# ProPrj_esp32_pressure_sensor_2026-01-10.net
KiCad netlist of a schematic drawn in EasyEDA Pro
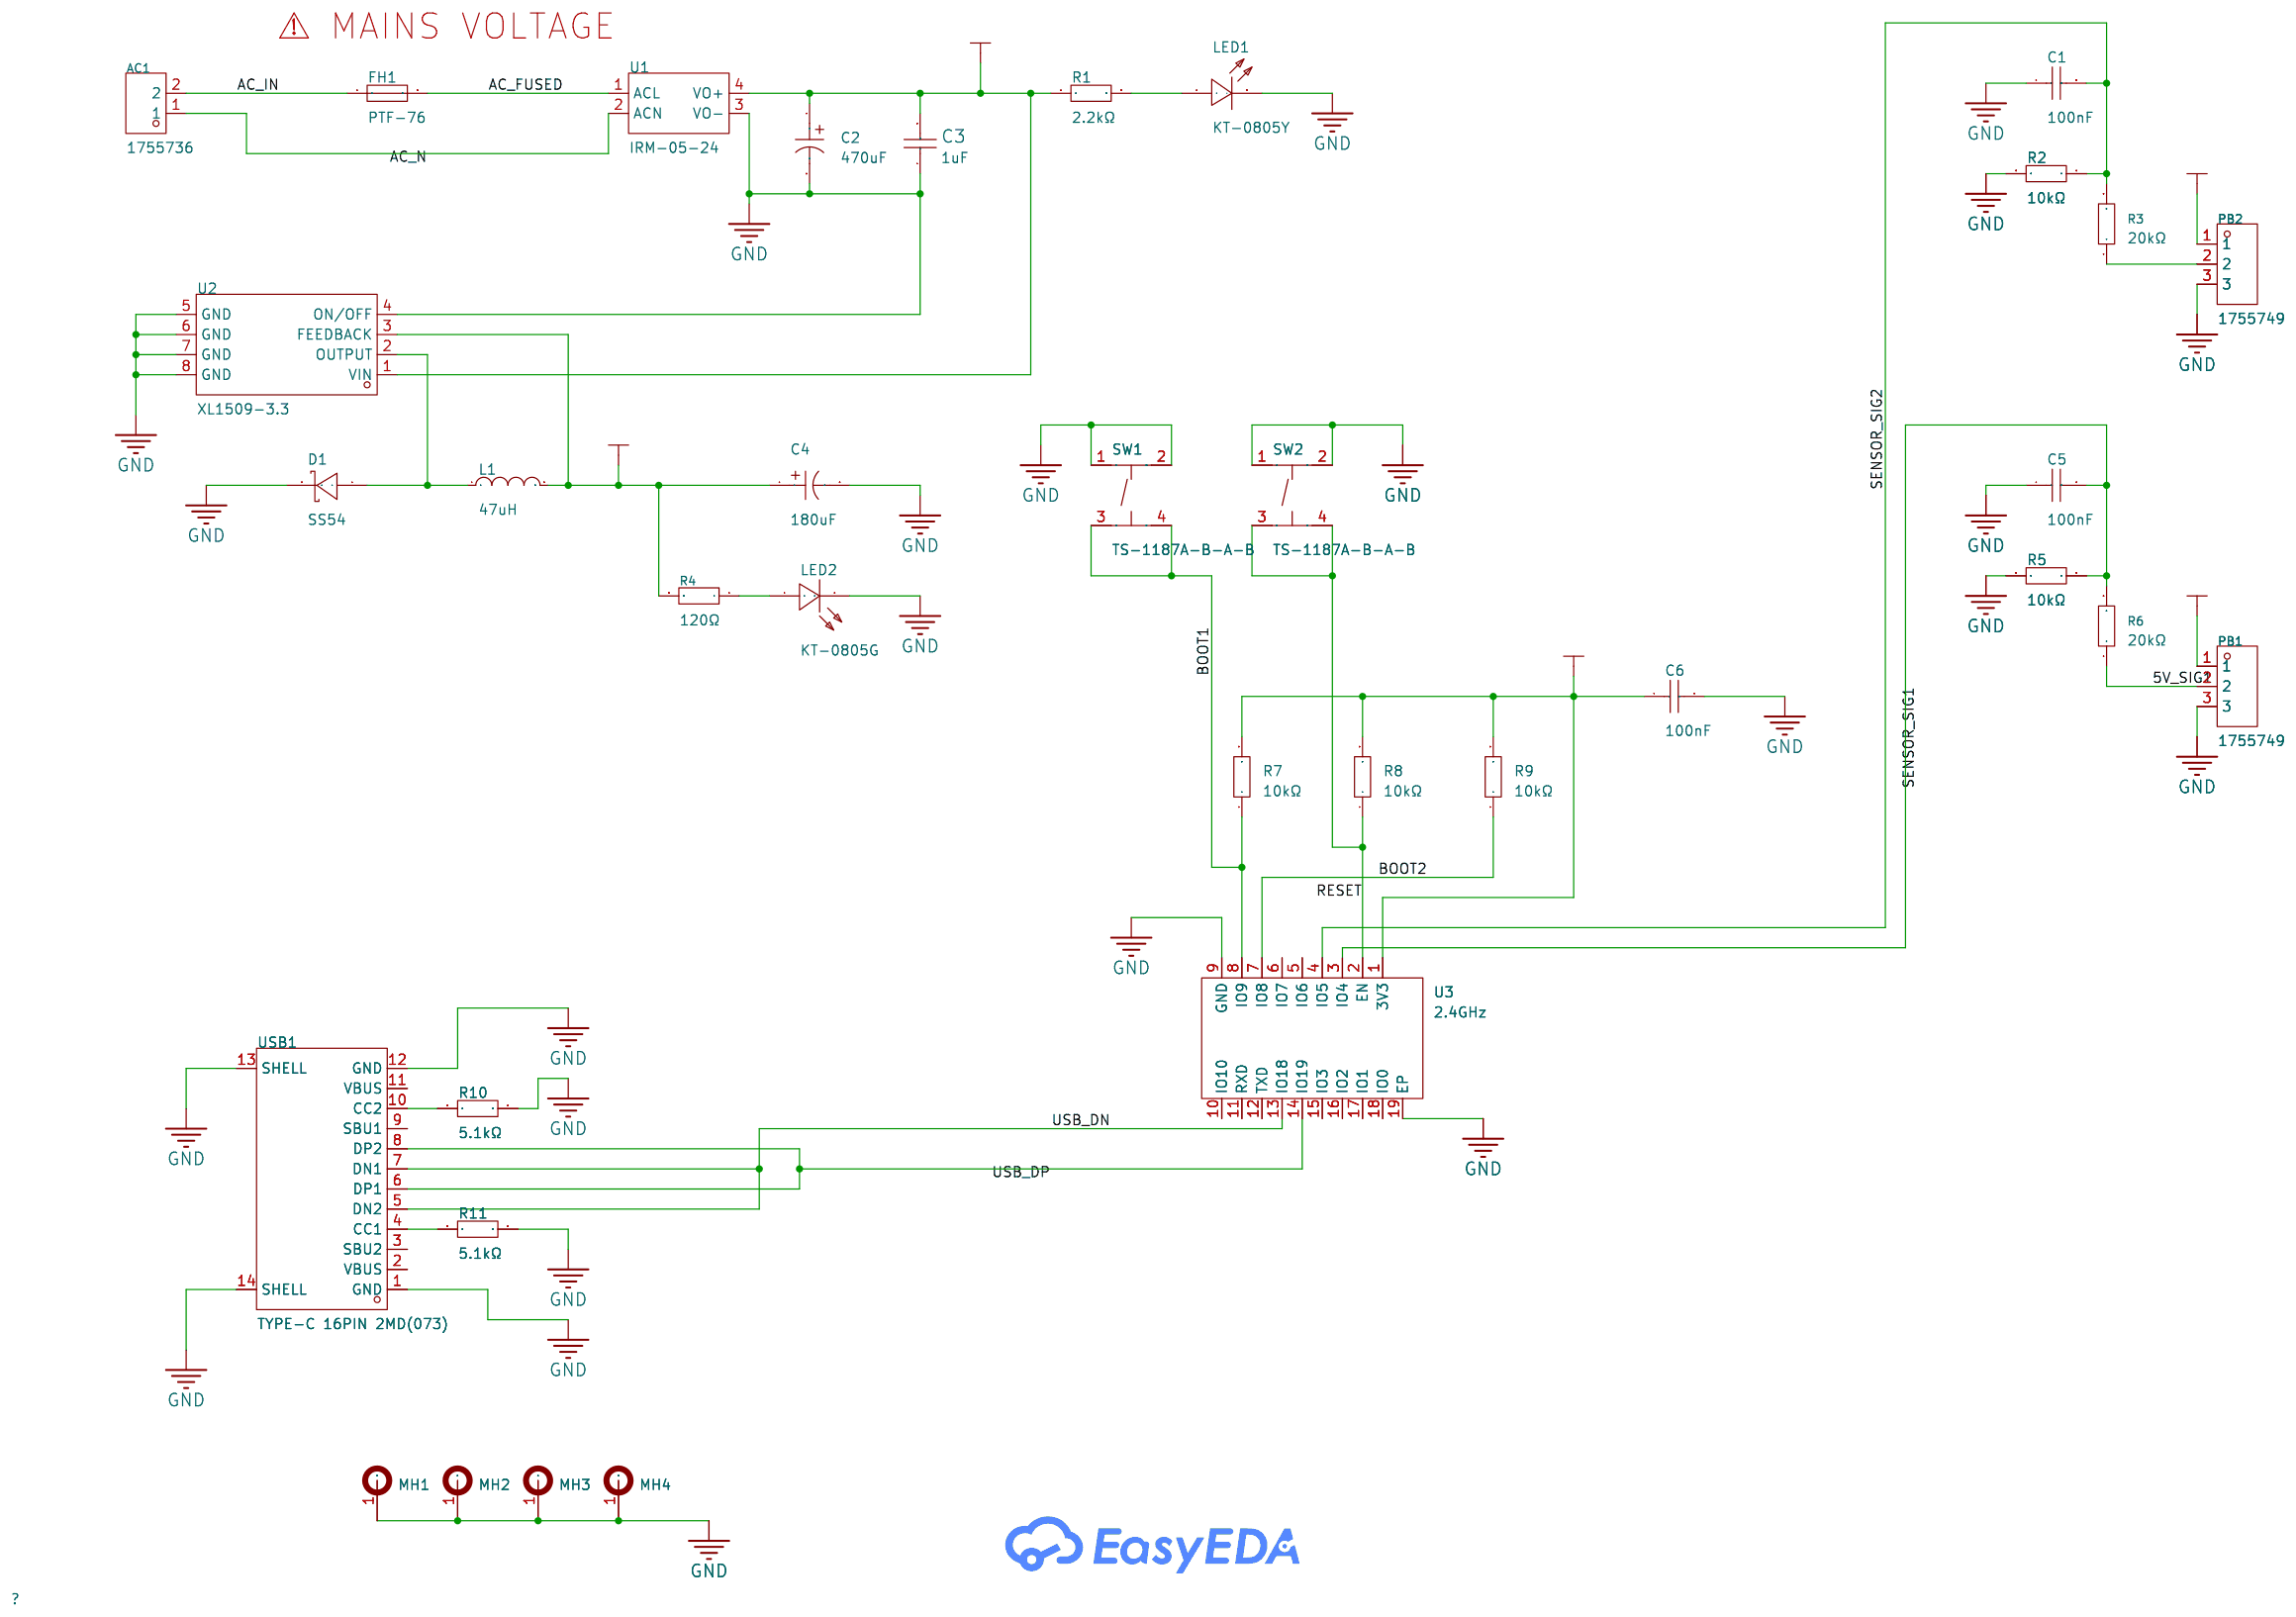
[diagram p0: schematic sheet]

(export (version "E")
  (design (tool "Eeschema 10.0.6"))
  (components
    (comp (ref "AC1")
      (value "1755736")
      (footprint "easyedapro:CONN-TH_1755736")
      (fields (field (name "Manufacturer") "Phoenix Contact(菲尼克斯)"))
      (libsource (lib "easyedapro") (part "1755736"))
    )
    (comp (ref "C1")
      (value "100nF")
      (footprint "easyedapro:C0805")
      (description "Capacitance:100nF Tolerance:±10% Tolerance:±10% Voltage Rating:100V Temperature Coefficient:X7R")
      (fields
        (field (name "Manufacturer Part") "CL21B104KCFNNNE")
        (field (name "Manufacturer") "SAMSUNG(三星)")
      )
      (libsource (lib "easyedapro") (part "CL21B104KCFNNNE"))
    )
    (comp (ref "C2")
      (value "470uF")
      (footprint "easyedapro:CAP-SMD_BD10.0-L10.3-W10.3-LS11.0-FD")
      (fields (field (name "Manufacturer Part") "JVE25V470M10X10") (field (name "Manufacturer") "JIERR(捷而瑞)"))
      (libsource (lib "easyedapro") (part "JVE25V470M10X10"))
    )
    (comp (ref "C3")
      (value "1uF")
      (footprint "easyedapro:C0805")
      (description "Capacitance:1uF Tolerance:±10% Tolerance:±10% Voltage Rating:50V Temperature Coefficient:X7R")
      (fields
        (field (name "Manufacturer Part") "CL21B105KBFNNNE")
        (field (name "Manufacturer") "SAMSUNG(三星)")
      )
      (libsource (lib "easyedapro") (part "CL21B105KBFNNNE"))
    )
    (comp (ref "C4")
      (value "180uF")
      (footprint "easyedapro:CAP-SMD_BD6.3-L6.6-W6.6-LS7.4-FD")
      (fields (field (name "Manufacturer Part") "RVT25V180M6X8") (field (name "Manufacturer") "JIERR(捷而瑞)"))
      (libsource (lib "easyedapro") (part "RVT25V180M6X8"))
    )
    (comp (ref "C5")
      (value "100nF")
      (footprint "easyedapro:C0805")
      (description "Capacitance:100nF Tolerance:±10% Tolerance:±10% Voltage Rating:100V Temperature Coefficient:X7R")
      (fields
        (field (name "Manufacturer Part") "CL21B104KCFNNNE")
        (field (name "Manufacturer") "SAMSUNG(三星)")
      )
      (libsource (lib "easyedapro") (part "CL21B104KCFNNNE"))
    )
    (comp (ref "C6")
      (value "100nF")
      (footprint "easyedapro:C0805")
      (description "Capacitance:100nF Tolerance:±10% Tolerance:±10% Voltage Rating:100V Temperature Coefficient:X7R")
      (fields
        (field (name "Manufacturer Part") "CL21B104KCFNNNE")
        (field (name "Manufacturer") "SAMSUNG(三星)")
      )
      (libsource (lib "easyedapro") (part "CL21B104KCFNNNE"))
    )
    (comp (ref "D1")
      (value "SS54")
      (footprint "easyedapro:SMA_L4.4-W2.8-LS5.4-R-RD")
      (fields (field (name "Manufacturer") "MDD(辰达半导体)"))
      (libsource (lib "easyedapro") (part "SS54_C22452"))
    )
    (comp (ref "FH1")
      (value "PTF-76")
      (footprint "easyedapro:FUSE-TH_L25.2-W9.8_PTF-76")
      (fields (field (name "Manufacturer") "XFCN(兴飞)"))
      (libsource (lib "easyedapro") (part "PTF-76"))
    )
    (comp (ref "L1")
      (value "47uH")
      (footprint "easyedapro:IND-SMD_L4.5-W4.0")
      (fields (field (name "Manufacturer Part") "CY43-47UH") (field (name "Manufacturer") "SHOU HAN(首韩)"))
      (libsource (lib "easyedapro") (part "CY43-47UH"))
    )
    (comp (ref "LED1")
      (value "KT-0805Y")
      (footprint "easyedapro:LED0805-R-RD")
      (fields (field (name "Manufacturer") "KENTO"))
      (libsource (lib "easyedapro") (part "17-21SUYC/TR8"))
    )
    (comp (ref "LED2")
      (value "KT-0805G")
      (footprint "easyedapro:LED0805-R-RD")
      (fields (field (name "Manufacturer") "KENTO"))
      (libsource (lib "easyedapro") (part "0805G (Green)"))
    )
    (comp (ref "MH1")
      (value "~")
      (footprint "easyedapro:MH_7.5x2.7mm")
      (libsource (lib "easyedapro") (part "MH_7.5x2.7mm"))
    )
    (comp (ref "MH2")
      (value "~")
      (footprint "easyedapro:MH_7.5x2.7mm")
      (libsource (lib "easyedapro") (part "MH_7.5x2.7mm"))
    )
    (comp (ref "MH3")
      (value "~")
      (footprint "easyedapro:MH_7.5x2.7mm")
      (libsource (lib "easyedapro") (part "MH_7.5x2.7mm"))
    )
    (comp (ref "MH4")
      (value "~")
      (footprint "easyedapro:MH_7.5x2.7mm")
      (libsource (lib "easyedapro") (part "MH_7.5x2.7mm"))
    )
    (comp (ref "PB1")
      (value "1755749")
      (footprint "easyedapro:CONN-TH_1755749")
      (fields (field (name "Manufacturer") "Phoenix Contact(菲尼克斯)"))
      (libsource (lib "easyedapro") (part "1755749"))
    )
    (comp (ref "PB2")
      (value "1755749")
      (footprint "easyedapro:CONN-TH_1755749")
      (fields (field (name "Manufacturer") "Phoenix Contact(菲尼克斯)"))
      (libsource (lib "easyedapro") (part "1755749"))
    )
    (comp (ref "R1")
      (value "2.2kΩ")
      (footprint "easyedapro:R0805")
      (fields
        (field (name "Manufacturer Part") "0805W8F2201T5E")
        (field (name "Manufacturer") "UNI-ROYAL(厚声)")
      )
      (libsource (lib "easyedapro") (part "0805W8F2201T5E"))
    )
    (comp (ref "R2")
      (value "10kΩ")
      (footprint "easyedapro:R0805")
      (fields
        (field (name "Manufacturer Part") "0805W8F1002T5E")
        (field (name "Manufacturer") "UNI-ROYAL(厚声)")
      )
      (libsource (lib "easyedapro") (part "0805W8F1002T5E"))
    )
    (comp (ref "R3")
      (value "20kΩ")
      (footprint "easyedapro:R0805")
      (fields
        (field (name "Manufacturer Part") "0805W8F2002T5E")
        (field (name "Manufacturer") "UNI-ROYAL(厚声)")
      )
      (libsource (lib "easyedapro") (part "0805W8F2002T5E"))
    )
    (comp (ref "R4")
      (value "120Ω")
      (footprint "easyedapro:R0805")
      (fields
        (field (name "Manufacturer Part") "0805W8F1200T5E")
        (field (name "Manufacturer") "UNI-ROYAL(厚声)")
      )
      (libsource (lib "easyedapro") (part "0805W8F1200T5E"))
    )
    (comp (ref "R5")
      (value "10kΩ")
      (footprint "easyedapro:R0805")
      (fields
        (field (name "Manufacturer Part") "0805W8F1002T5E")
        (field (name "Manufacturer") "UNI-ROYAL(厚声)")
      )
      (libsource (lib "easyedapro") (part "0805W8F1002T5E"))
    )
    (comp (ref "R6")
      (value "20kΩ")
      (footprint "easyedapro:R0805")
      (fields
        (field (name "Manufacturer Part") "0805W8F2002T5E")
        (field (name "Manufacturer") "UNI-ROYAL(厚声)")
      )
      (libsource (lib "easyedapro") (part "0805W8F2002T5E"))
    )
    (comp (ref "R7")
      (value "10kΩ")
      (footprint "easyedapro:R0805")
      (fields
        (field (name "Manufacturer Part") "0805W8F1002T5E")
        (field (name "Manufacturer") "UNI-ROYAL(厚声)")
      )
      (libsource (lib "easyedapro") (part "0805W8F1002T5E"))
    )
    (comp (ref "R8")
      (value "10kΩ")
      (footprint "easyedapro:R0805")
      (fields
        (field (name "Manufacturer Part") "0805W8F1002T5E")
        (field (name "Manufacturer") "UNI-ROYAL(厚声)")
      )
      (libsource (lib "easyedapro") (part "0805W8F1002T5E"))
    )
    (comp (ref "R9")
      (value "10kΩ")
      (footprint "easyedapro:R0805")
      (fields
        (field (name "Manufacturer Part") "0805W8F1002T5E")
        (field (name "Manufacturer") "UNI-ROYAL(厚声)")
      )
      (libsource (lib "easyedapro") (part "0805W8F1002T5E"))
    )
    (comp (ref "R10")
      (value "5.1kΩ")
      (footprint "easyedapro:R0805")
      (fields
        (field (name "Manufacturer Part") "0805W8F5101T5E")
        (field (name "Manufacturer") "UNI-ROYAL(厚声)")
      )
      (libsource (lib "easyedapro") (part "0805W8F5101T5E"))
    )
    (comp (ref "R11")
      (value "5.1kΩ")
      (footprint "easyedapro:R0805")
      (fields
        (field (name "Manufacturer Part") "0805W8F5101T5E")
        (field (name "Manufacturer") "UNI-ROYAL(厚声)")
      )
      (libsource (lib "easyedapro") (part "0805W8F5101T5E"))
    )
    (comp (ref "SW1")
      (value "TS-1187A-B-A-B")
      (footprint "easyedapro:SW-SMD_4P-L5.1-W5.1-P3.70-LS6.5-TL_H1.5")
      (fields (field (name "Manufacturer") "XKB Connection(中国星坤)"))
      (libsource (lib "easyedapro") (part "TS-1187A-B-A-B"))
    )
    (comp (ref "SW2")
      (value "TS-1187A-B-A-B")
      (footprint "easyedapro:SW-SMD_4P-L5.1-W5.1-P3.70-LS6.5-TL_H1.5")
      (fields (field (name "Manufacturer") "XKB Connection(中国星坤)"))
      (libsource (lib "easyedapro") (part "TS-1187A-B-A-B"))
    )
    (comp (ref "U1")
      (value "IRM-05-24")
      (footprint "easyedapro:PWRM-TH_IRM-05-XX")
      (fields (field (name "Manufacturer") "MW(明纬)"))
      (libsource (lib "easyedapro") (part "IRM-05-24"))
    )
    (comp (ref "U2")
      (value "XL1509-3.3")
      (footprint "easyedapro:SOIC-8_L4.9-W3.9-P1.27-LS6.0-BL")
      (fields (field (name "Manufacturer") "UMW(友台半导体)"))
      (libsource (lib "easyedapro") (part "XL1509-3.3"))
    )
    (comp (ref "U3")
      (value "2.4GHz")
      (footprint "easyedapro:BULETM-SMD_ESPRESSIF_ESP32-C3-WROOM-02-N4-4MB")
      (fields
        (field (name "Manufacturer Part") "ESP32-C3-WROOM-02-N4")
        (field (name "Manufacturer") "ESPRESSIF(乐鑫)")
      )
      (libsource (lib "easyedapro") (part "ESP32-C3-WROOM-02-N4(4MB)"))
    )
    (comp (ref "USB1")
      (value "TYPE-C 16PIN 2MD(073)")
      (footprint "easyedapro:USB-C-SMD_TYPE-C-6PIN-2MD-073")
      (fields (field (name "Manufacturer") "SHOU HAN(首韩)"))
      (libsource (lib "easyedapro") (part "TYPE-C 16PIN 2MD(073)"))
    )
  )
  (nets
    (net (code "1") (name "+3.3V") (class "Default")
      (node (ref "C4") (pin "1") (pinfunction "1_1") (pintype "input"))
      (node (ref "C6") (pin "1") (pinfunction "1_1") (pintype "input"))
      (node (ref "L1") (pin "2") (pinfunction "2_2") (pintype "unspecified"))
      (node (ref "R4") (pin "2") (pinfunction "2_2") (pintype "input"))
      (node (ref "R7") (pin "2") (pinfunction "2_2") (pintype "input"))
      (node (ref "R8") (pin "2") (pinfunction "2_2") (pintype "input"))
      (node (ref "R9") (pin "2") (pinfunction "2_2") (pintype "input"))
      (node (ref "U2") (pin "3") (pinfunction "FEEDBACK_3") (pintype "unspecified"))
      (node (ref "U3") (pin "1") (pinfunction "3V3_1") (pintype "unspecified"))
    )
    (net (code "2") (name "+24V") (class "Default")
      (node (ref "C2") (pin "1") (pinfunction "1_1") (pintype "input"))
      (node (ref "C3") (pin "2") (pinfunction "2_2") (pintype "input"))
      (node (ref "PB1") (pin "1") (pinfunction "1_1") (pintype "input"))
      (node (ref "PB2") (pin "1") (pinfunction "1_1") (pintype "input"))
      (node (ref "R1") (pin "1") (pinfunction "1_1") (pintype "input"))
      (node (ref "U1") (pin "4") (pinfunction "VO+_4") (pintype "unspecified"))
      (node (ref "U2") (pin "1") (pinfunction "VIN_1") (pintype "unspecified"))
    )
    (net (code "3") (name "/5V_SIG1") (class "Default")
      (node (ref "PB1") (pin "2") (pinfunction "2_2") (pintype "input"))
      (node (ref "R6") (pin "1") (pinfunction "1_1") (pintype "input"))
    )
    (net (code "4") (name "/AC_FUSED") (class "Default")
      (node (ref "FH1") (pin "2") (pinfunction "2_2") (pintype "unspecified"))
      (node (ref "U1") (pin "1") (pinfunction "ACL_1") (pintype "unspecified"))
    )
    (net (code "5") (name "/AC_IN") (class "Default")
      (node (ref "AC1") (pin "2") (pinfunction "2_2") (pintype "input"))
      (node (ref "FH1") (pin "1") (pinfunction "1_1") (pintype "unspecified"))
    )
    (net (code "6") (name "/AC_N") (class "Default")
      (node (ref "AC1") (pin "1") (pinfunction "1_1") (pintype "input"))
      (node (ref "U1") (pin "2") (pinfunction "ACN_2") (pintype "unspecified"))
    )
    (net (code "7") (name "/BOOT1") (class "Default")
      (node (ref "R7") (pin "1") (pinfunction "1_1") (pintype "input"))
      (node (ref "SW1") (pin "3") (pinfunction "C_3") (pintype "unspecified"))
      (node (ref "SW1") (pin "4") (pinfunction "D_4") (pintype "unspecified"))
      (node (ref "U3") (pin "8") (pinfunction "IO9_8") (pintype "unspecified"))
    )
    (net (code "8") (name "/BOOT2") (class "Default")
      (node (ref "R9") (pin "1") (pinfunction "1_1") (pintype "input"))
      (node (ref "U3") (pin "7") (pinfunction "IO8_7") (pintype "unspecified"))
    )
    (net (code "9") (name "/RESET") (class "Default")
      (node (ref "R8") (pin "1") (pinfunction "1_1") (pintype "input"))
      (node (ref "SW2") (pin "3") (pinfunction "C_3") (pintype "unspecified"))
      (node (ref "SW2") (pin "4") (pinfunction "D_4") (pintype "unspecified"))
      (node (ref "U3") (pin "2") (pinfunction "EN_2") (pintype "unspecified"))
    )
    (net (code "10") (name "/SENSOR_SIG1") (class "Default")
      (node (ref "C5") (pin "2") (pinfunction "2_2") (pintype "input"))
      (node (ref "R5") (pin "1") (pinfunction "1_1") (pintype "input"))
      (node (ref "R6") (pin "2") (pinfunction "2_2") (pintype "input"))
      (node (ref "U3") (pin "3") (pinfunction "IO4_3") (pintype "unspecified"))
    )
    (net (code "11") (name "/SENSOR_SIG2") (class "Default")
      (node (ref "C1") (pin "2") (pinfunction "2_2") (pintype "input"))
      (node (ref "R2") (pin "1") (pinfunction "1_1") (pintype "input"))
      (node (ref "R3") (pin "2") (pinfunction "2_2") (pintype "input"))
      (node (ref "U3") (pin "4") (pinfunction "IO5_4") (pintype "unspecified"))
    )
    (net (code "12") (name "/USB_DN") (class "Default")
      (node (ref "U3") (pin "13") (pinfunction "IO18_13") (pintype "unspecified"))
      (node (ref "USB1") (pin "5") (pinfunction "DN2_5") (pintype "unspecified"))
      (node (ref "USB1") (pin "7") (pinfunction "DN1_7") (pintype "unspecified"))
    )
    (net (code "13") (name "/USB_DP") (class "Default")
      (node (ref "U3") (pin "14") (pinfunction "IO19_14") (pintype "unspecified"))
      (node (ref "USB1") (pin "6") (pinfunction "DP1_6") (pintype "unspecified"))
      (node (ref "USB1") (pin "8") (pinfunction "DP2_8") (pintype "unspecified"))
    )
    (net (code "14") (name "GND") (class "Default")
      (node (ref "C1") (pin "1") (pinfunction "1_1") (pintype "input"))
      (node (ref "C2") (pin "2") (pinfunction "2_2") (pintype "input"))
      (node (ref "C3") (pin "1") (pinfunction "1_1") (pintype "input"))
      (node (ref "C4") (pin "2") (pinfunction "2_2") (pintype "input"))
      (node (ref "C5") (pin "1") (pinfunction "1_1") (pintype "input"))
      (node (ref "C6") (pin "2") (pinfunction "2_2") (pintype "input"))
      (node (ref "D1") (pin "2") (pinfunction "K_2") (pintype "unspecified"))
      (node (ref "LED1") (pin "2") (pinfunction "-_2") (pintype "unspecified"))
      (node (ref "LED2") (pin "2") (pinfunction "K_2") (pintype "unspecified"))
      (node (ref "MH1") (pin "1") (pinfunction "1_1") (pintype "input"))
      (node (ref "MH2") (pin "1") (pinfunction "1_1") (pintype "input"))
      (node (ref "MH3") (pin "1") (pinfunction "1_1") (pintype "input"))
      (node (ref "MH4") (pin "1") (pinfunction "1_1") (pintype "input"))
      (node (ref "PB1") (pin "3") (pinfunction "3_3") (pintype "input"))
      (node (ref "PB2") (pin "3") (pinfunction "3_3") (pintype "input"))
      (node (ref "R10") (pin "1") (pinfunction "1_1") (pintype "input"))
      (node (ref "R11") (pin "1") (pinfunction "1_1") (pintype "input"))
      (node (ref "R2") (pin "2") (pinfunction "2_2") (pintype "input"))
      (node (ref "R5") (pin "2") (pinfunction "2_2") (pintype "input"))
      (node (ref "SW1") (pin "1") (pinfunction "A_1") (pintype "unspecified"))
      (node (ref "SW1") (pin "2") (pinfunction "B_2") (pintype "unspecified"))
      (node (ref "SW2") (pin "1") (pinfunction "A_1") (pintype "unspecified"))
      (node (ref "SW2") (pin "2") (pinfunction "B_2") (pintype "unspecified"))
      (node (ref "U1") (pin "3") (pinfunction "VO-_3") (pintype "unspecified"))
      (node (ref "U2") (pin "4") (pinfunction "ON/OFF_4") (pintype "unspecified"))
      (node (ref "U2") (pin "5") (pinfunction "GND_5") (pintype "unspecified"))
      (node (ref "U2") (pin "6") (pinfunction "GND_6") (pintype "unspecified"))
      (node (ref "U2") (pin "7") (pinfunction "GND_7") (pintype "unspecified"))
      (node (ref "U2") (pin "8") (pinfunction "GND_8") (pintype "unspecified"))
      (node (ref "U3") (pin "19") (pinfunction "EP_19") (pintype "unspecified"))
      (node (ref "U3") (pin "9") (pinfunction "GND_9") (pintype "unspecified"))
      (node (ref "USB1") (pin "1") (pinfunction "GND_1") (pintype "unspecified"))
      (node (ref "USB1") (pin "12") (pinfunction "GND_12") (pintype "unspecified"))
      (node (ref "USB1") (pin "13") (pinfunction "SHELL_13") (pintype "unspecified"))
      (node (ref "USB1") (pin "14") (pinfunction "SHELL_14") (pintype "unspecified"))
    )
    (net (code "15") (name "Net-(D1-A)") (class "Default")
      (node (ref "D1") (pin "1") (pinfunction "A_1") (pintype "unspecified"))
      (node (ref "L1") (pin "1") (pinfunction "1_1") (pintype "unspecified"))
      (node (ref "U2") (pin "2") (pinfunction "OUTPUT_2") (pintype "unspecified"))
    )
    (net (code "16") (name "Net-(LED1-+)") (class "Default")
      (node (ref "LED1") (pin "1") (pinfunction "+_1") (pintype "unspecified"))
      (node (ref "R1") (pin "2") (pinfunction "2_2") (pintype "input"))
    )
    (net (code "17") (name "Net-(LED2-A)") (class "Default")
      (node (ref "LED2") (pin "1") (pinfunction "A_1") (pintype "unspecified"))
      (node (ref "R4") (pin "1") (pinfunction "1_1") (pintype "input"))
    )
    (net (code "18") (name "Net-(PB2-Pad2)") (class "Default")
      (node (ref "PB2") (pin "2") (pinfunction "2_2") (pintype "input"))
      (node (ref "R3") (pin "1") (pinfunction "1_1") (pintype "input"))
    )
    (net (code "19") (name "Net-(USB1-CC1)") (class "Default")
      (node (ref "R11") (pin "2") (pinfunction "2_2") (pintype "input"))
      (node (ref "USB1") (pin "4") (pinfunction "CC1_4") (pintype "unspecified"))
    )
    (net (code "20") (name "Net-(USB1-CC2)") (class "Default")
      (node (ref "R10") (pin "2") (pinfunction "2_2") (pintype "input"))
      (node (ref "USB1") (pin "10") (pinfunction "CC2_10") (pintype "unspecified"))
    )
    (net (code "21") (name "unconnected-(U3-IO0-Pad18)") (class "Default")
      (node (ref "U3") (pin "18") (pinfunction "IO0_18") (pintype "unspecified"))
    )
    (net (code "22") (name "unconnected-(U3-IO1-Pad17)") (class "Default")
      (node (ref "U3") (pin "17") (pinfunction "IO1_17") (pintype "unspecified"))
    )
    (net (code "23") (name "unconnected-(U3-IO2-Pad16)") (class "Default")
      (node (ref "U3") (pin "16") (pinfunction "IO2_16") (pintype "unspecified"))
    )
    (net (code "24") (name "unconnected-(U3-IO3-Pad15)") (class "Default")
      (node (ref "U3") (pin "15") (pinfunction "IO3_15") (pintype "unspecified"))
    )
    (net (code "25") (name "unconnected-(U3-IO6-Pad5)") (class "Default")
      (node (ref "U3") (pin "5") (pinfunction "IO6_5") (pintype "unspecified"))
    )
    (net (code "26") (name "unconnected-(U3-IO7-Pad6)") (class "Default")
      (node (ref "U3") (pin "6") (pinfunction "IO7_6") (pintype "unspecified"))
    )
    (net (code "27") (name "unconnected-(U3-IO10-Pad10)") (class "Default")
      (node (ref "U3") (pin "10") (pinfunction "IO10_10") (pintype "unspecified"))
    )
    (net (code "28") (name "unconnected-(U3-RXD-Pad11)") (class "Default")
      (node (ref "U3") (pin "11") (pinfunction "RXD_11") (pintype "unspecified"))
    )
    (net (code "29") (name "unconnected-(U3-TXD-Pad12)") (class "Default")
      (node (ref "U3") (pin "12") (pinfunction "TXD_12") (pintype "unspecified"))
    )
    (net (code "30") (name "unconnected-(USB1-SBU1-Pad9)") (class "Default")
      (node (ref "USB1") (pin "9") (pinfunction "SBU1_9") (pintype "unspecified"))
    )
    (net (code "31") (name "unconnected-(USB1-SBU2-Pad3)") (class "Default")
      (node (ref "USB1") (pin "3") (pinfunction "SBU2_3") (pintype "unspecified"))
    )
    (net (code "32") (name "unconnected-(USB1-VBUS-Pad2)") (class "Default")
      (node (ref "USB1") (pin "2") (pinfunction "VBUS_2") (pintype "unspecified"))
    )
    (net (code "33") (name "unconnected-(USB1-VBUS-Pad11)") (class "Default")
      (node (ref "USB1") (pin "11") (pinfunction "VBUS_11") (pintype "unspecified"))
    )
  )
)
